# Schematic.net
KiCad netlist of a schematic drawn in EAGLE
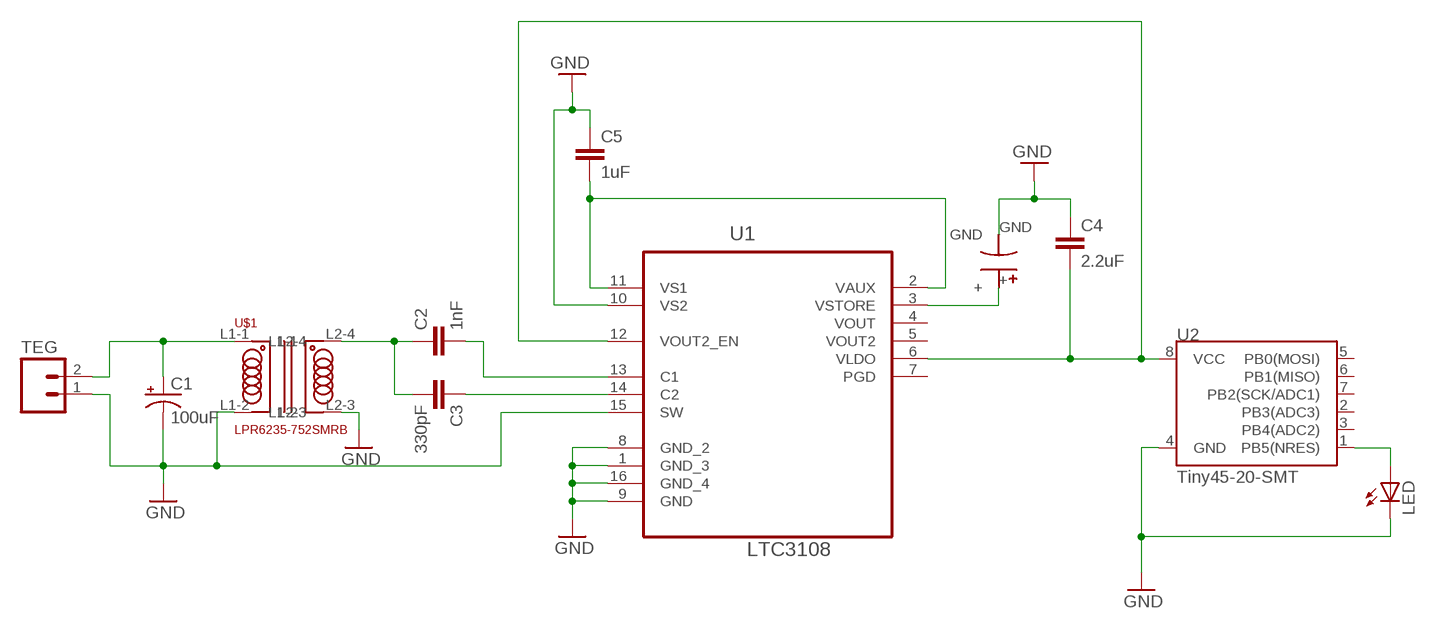
[diagram p0: schematic, sheet 1]

(export (version "E")
  (design (tool "Eeschema 10.0.6"))
  (components
    (comp (ref "C1")
      (value "100uF")
      (footprint "eagle-import:EIA3216")
      (libsource (lib "eagle-import") (part "10UF-16V-10%(TANT)"))
    )
    (comp (ref "C2")
      (value "1nF")
      (footprint "eagle-import:0603-CAP")
      (libsource (lib "eagle-import") (part "CAP0603-CAP"))
    )
    (comp (ref "C3")
      (value "330pF")
      (footprint "eagle-import:0603-CAP")
      (libsource (lib "eagle-import") (part "CAP0603-CAP"))
    )
    (comp (ref "C4")
      (value "2.2uF")
      (footprint "eagle-import:0603-CAP")
      (libsource (lib "eagle-import") (part "CAP0603-CAP"))
    )
    (comp (ref "C5")
      (value "1uF")
      (footprint "eagle-import:0603-CAP")
      (libsource (lib "eagle-import") (part "CAP0603-CAP"))
    )
    (comp (ref "LED")
      (value "LEDCHIPLED_0805")
      (footprint "eagle-import:CHIPLED_0805")
      (libsource (lib "eagle-import") (part "LEDCHIPLED_0805"))
    )
    (comp (ref "TEG")
      (value "M02LOCK")
      (footprint "eagle-import:1X02_LOCK")
      (libsource (lib "eagle-import") (part "M02LOCK"))
    )
    (comp (ref "U$1")
      (value "LPR6235-752SMRB")
      (footprint "eagle-import:LPR6235-752SMRB")
      (libsource (lib "eagle-import") (part "LPR6235-752SMRB"))
    )
    (comp (ref "U$2")
      (value "FC0V104FTBR24")
      (footprint "eagle-import:FC0V104ZFTBR24")
      (libsource (lib "eagle-import") (part "FC0V104FTBR24"))
    )
    (comp (ref "U1")
      (value "LTC3108")
      (footprint "eagle-import:SOP63P600X175-16N")
      (fields (field (name "MPN") "LTC3108IGN#PBF"))
      (libsource (lib "eagle-import") (part "LTC3108IGNPBF"))
    )
    (comp (ref "U2")
      (value "Tiny45-20-SMT")
      (footprint "eagle-import:SO08-EIAJ")
      (libsource (lib "eagle-import") (part "ATTINY45TINY45-20-SMT"))
    )
  )
  (nets
    (net (code "1") (name "GND") (class "Default")
      (node (ref "C1") (pin "C") (pinfunction "-_C") (pintype "passive"))
      (node (ref "C4") (pin "1") (pinfunction "1_1") (pintype "passive"))
      (node (ref "C5") (pin "1") (pinfunction "1_1") (pintype "passive"))
      (node (ref "LED") (pin "C") (pinfunction "C_C") (pintype "passive"))
      (node (ref "TEG") (pin "1") (pinfunction "1_1") (pintype "passive"))
      (node (ref "U$1") (pin "L1-2") (pinfunction "L1-2_L1-2") (pintype "bidirectional"))
      (node (ref "U$1") (pin "L2-3") (pinfunction "L2-3_L2-3") (pintype "bidirectional"))
      (node (ref "U$2") (pin "GND") (pinfunction "GND_GND") (pintype "bidirectional"))
      (node (ref "U1") (pin "1") (pinfunction "GND_3_1") (pintype "passive"))
      (node (ref "U1") (pin "10") (pinfunction "VS2_10") (pintype "input"))
      (node (ref "U1") (pin "15") (pinfunction "SW_15") (pintype "passive"))
      (node (ref "U1") (pin "16") (pinfunction "GND_4_16") (pintype "passive"))
      (node (ref "U1") (pin "8") (pinfunction "GND_2_8") (pintype "passive"))
      (node (ref "U1") (pin "9") (pinfunction "GND_9") (pintype "passive"))
      (node (ref "U2") (pin "4") (pinfunction "GND_4") (pintype "bidirectional"))
    )
    (net (code "2") (name "Net-(C1-+)") (class "Default")
      (node (ref "C1") (pin "A") (pinfunction "+_A") (pintype "passive"))
      (node (ref "TEG") (pin "2") (pinfunction "2_2") (pintype "passive"))
      (node (ref "U$1") (pin "L1-1") (pinfunction "L1-1_L1-1") (pintype "bidirectional"))
    )
    (net (code "3") (name "Net-(C2-Pad1)") (class "Default")
      (node (ref "C2") (pin "1") (pinfunction "1_1") (pintype "passive"))
      (node (ref "C3") (pin "2") (pinfunction "2_2") (pintype "passive"))
      (node (ref "U$1") (pin "L2-4") (pinfunction "L2-4_L2-4") (pintype "bidirectional"))
    )
    (net (code "4") (name "Net-(U1-C1)") (class "Default")
      (node (ref "C2") (pin "2") (pinfunction "2_2") (pintype "passive"))
      (node (ref "U1") (pin "13") (pinfunction "C1_13") (pintype "input"))
    )
    (net (code "5") (name "Net-(U1-C2)") (class "Default")
      (node (ref "C3") (pin "1") (pinfunction "1_1") (pintype "passive"))
      (node (ref "U1") (pin "14") (pinfunction "C2_14") (pintype "input"))
    )
    (net (code "6") (name "Net-(U1-VAUX)") (class "Default")
      (node (ref "C5") (pin "2") (pinfunction "2_2") (pintype "passive"))
      (node (ref "U1") (pin "11") (pinfunction "VS1_11") (pintype "input"))
      (node (ref "U1") (pin "2") (pinfunction "VAUX_2") (pintype "output"))
    )
    (net (code "7") (name "Net-(U1-VLDO)") (class "Default")
      (node (ref "C4") (pin "2") (pinfunction "2_2") (pintype "passive"))
      (node (ref "U1") (pin "12") (pinfunction "VOUT2_EN_12") (pintype "input"))
      (node (ref "U1") (pin "6") (pinfunction "VLDO_6") (pintype "output"))
      (node (ref "U2") (pin "8") (pinfunction "VCC_8") (pintype "bidirectional"))
    )
    (net (code "8") (name "Net-(U1-VSTORE)") (class "Default")
      (node (ref "U$2") (pin "+") (pinfunction "+_+") (pintype "bidirectional"))
      (node (ref "U1") (pin "3") (pinfunction "VSTORE_3") (pintype "output"))
    )
    (net (code "9") (name "Net-(U2-PB5(NRES))") (class "Default")
      (node (ref "LED") (pin "A") (pinfunction "A_A") (pintype "passive"))
      (node (ref "U2") (pin "1") (pinfunction "PB5(NRES)_1") (pintype "bidirectional"))
    )
    (net (code "10") (name "unconnected-(U1-PGD-Pad7)") (class "Default")
      (node (ref "U1") (pin "7") (pinfunction "PGD_7") (pintype "output"))
    )
    (net (code "11") (name "unconnected-(U1-VOUT-Pad4)") (class "Default")
      (node (ref "U1") (pin "4") (pinfunction "VOUT_4") (pintype "output"))
    )
    (net (code "12") (name "unconnected-(U1-VOUT2-Pad5)") (class "Default")
      (node (ref "U1") (pin "5") (pinfunction "VOUT2_5") (pintype "output"))
    )
    (net (code "13") (name "unconnected-(U2-PB0(MOSI)-Pad5)") (class "Default")
      (node (ref "U2") (pin "5") (pinfunction "PB0(MOSI)_5") (pintype "bidirectional"))
    )
    (net (code "14") (name "unconnected-(U2-PB1(MISO)-Pad6)") (class "Default")
      (node (ref "U2") (pin "6") (pinfunction "PB1(MISO)_6") (pintype "bidirectional"))
    )
    (net (code "15") (name "unconnected-(U2-PB2(SCK{slash}ADC1)-Pad7)") (class "Default")
      (node (ref "U2") (pin "7") (pinfunction "PB2(SCK/ADC1)_7") (pintype "bidirectional"))
    )
    (net (code "16") (name "unconnected-(U2-PB3(ADC3)-Pad2)") (class "Default")
      (node (ref "U2") (pin "2") (pinfunction "PB3(ADC3)_2") (pintype "bidirectional"))
    )
    (net (code "17") (name "unconnected-(U2-PB4(ADC2)-Pad3)") (class "Default")
      (node (ref "U2") (pin "3") (pinfunction "PB4(ADC2)_3") (pintype "bidirectional"))
    )
  )
)
